# WiFi_Board_R1_0.net
KiCad netlist of a schematic drawn in EAGLE
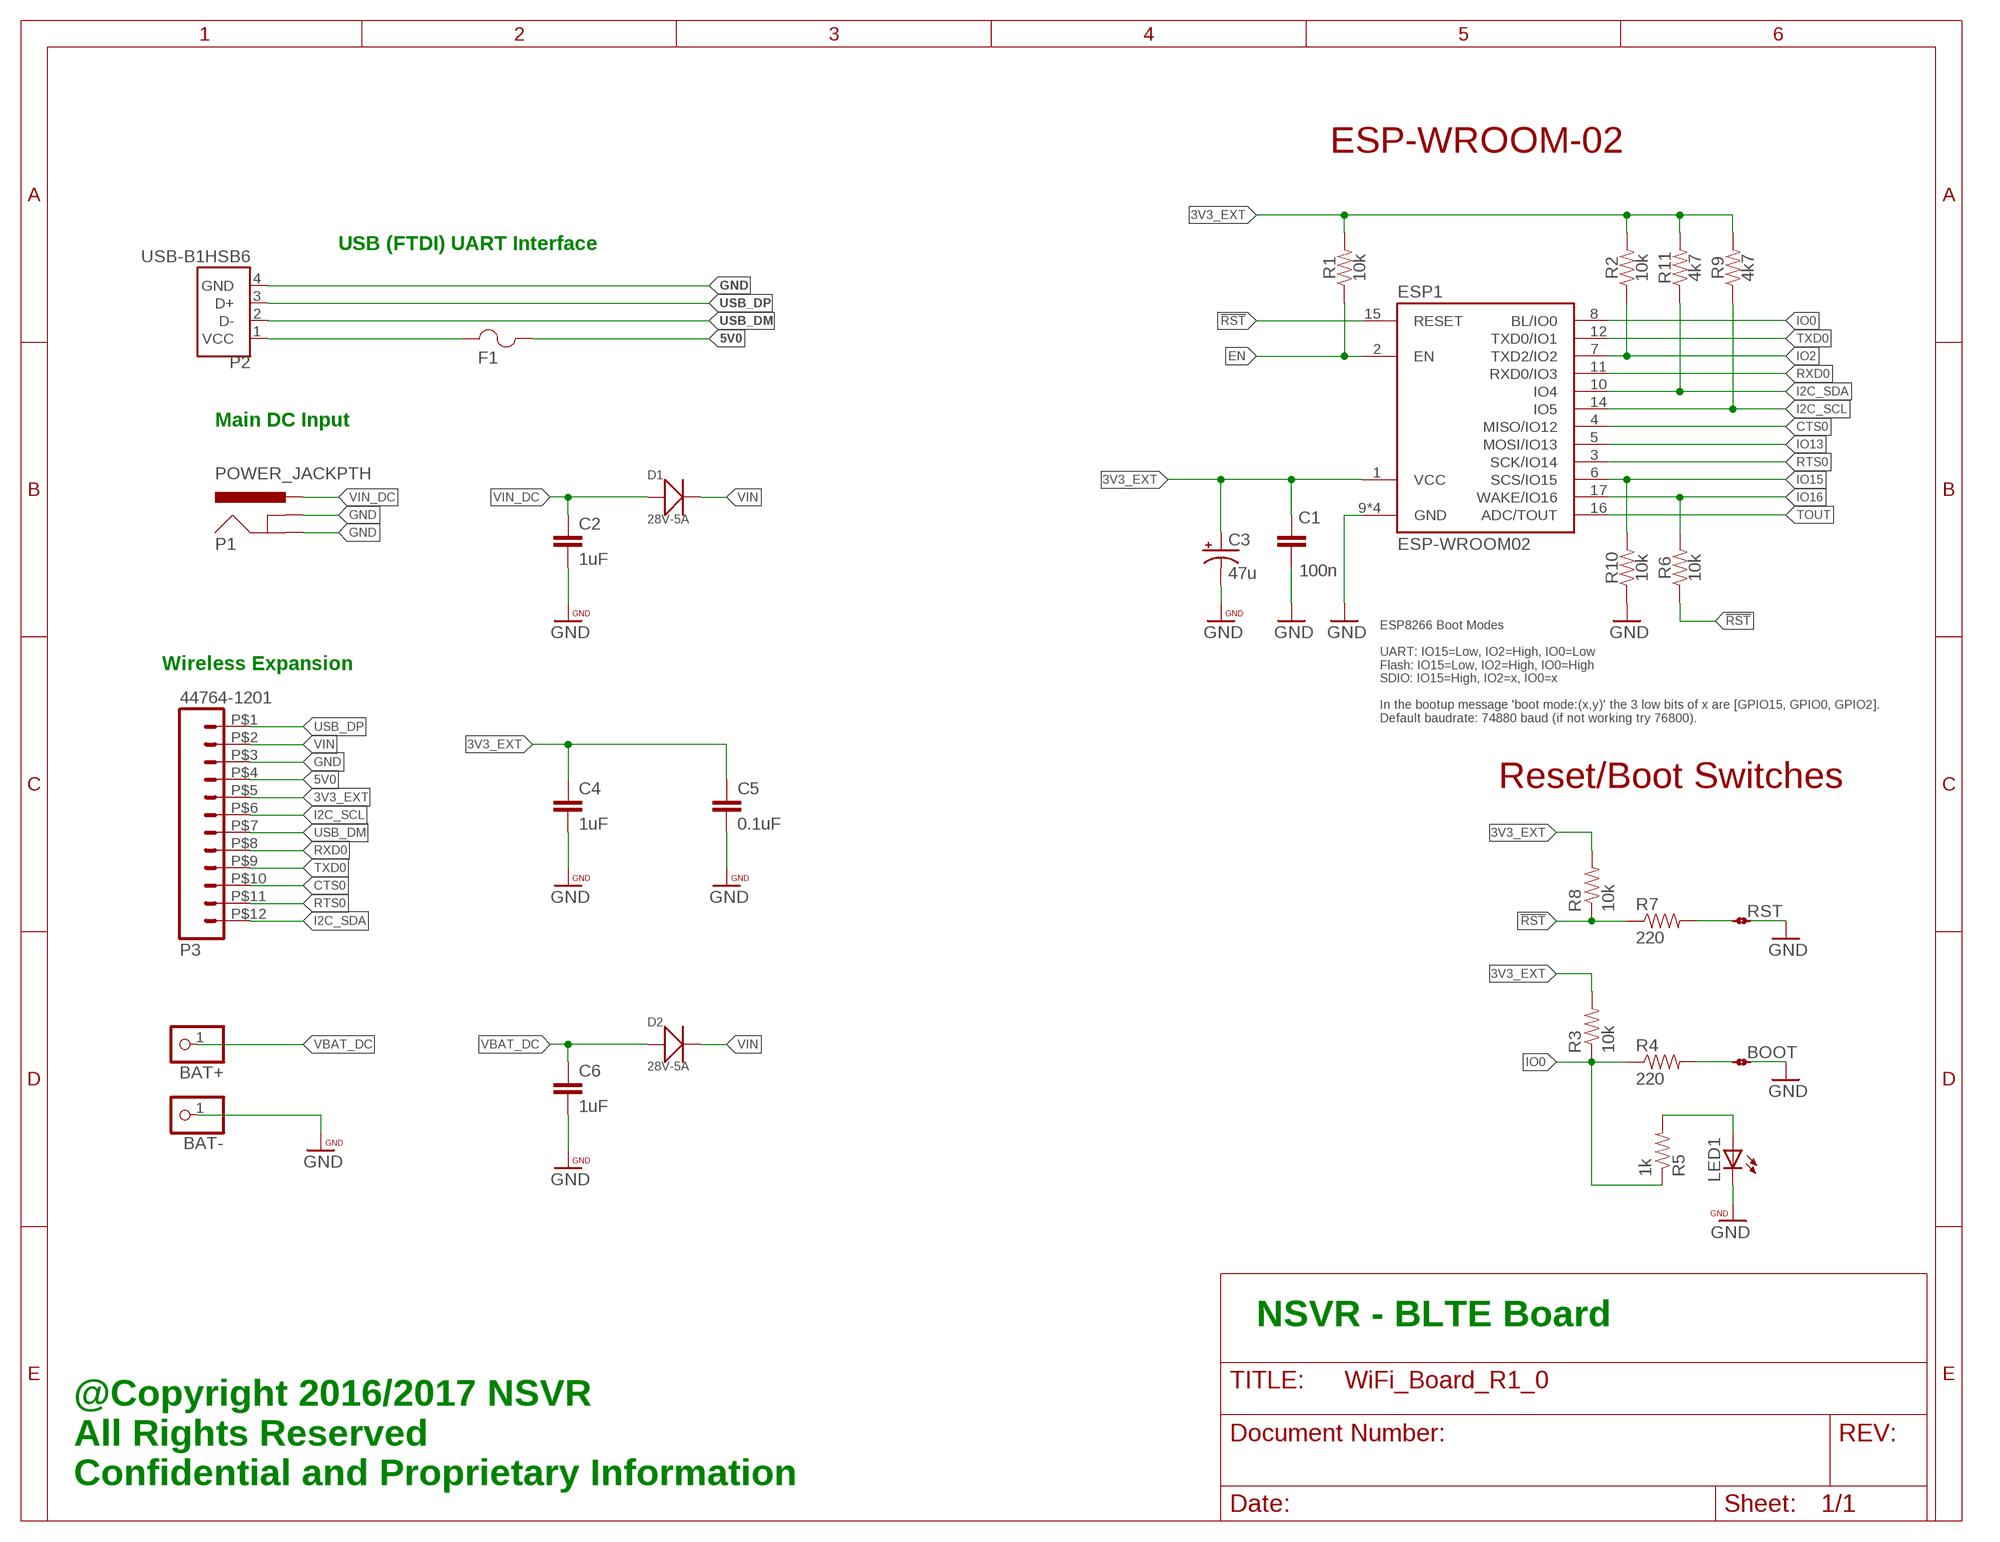
[diagram p0: schematic, sheet 1]

(export (version "E")
  (design (tool "Eeschema 10.0.6"))
  (components
    (comp (ref "BAT+")
      (value "WPAD-1-PTH")
      (footprint "eagle-import:WPAD-1-PTH-2.54")
      (libsource (lib "eagle-import") (part "WPAD-1-PTH"))
    )
    (comp (ref "BAT-")
      (value "WPAD-1-PTH")
      (footprint "eagle-import:WPAD-1-PTH-2.54")
      (libsource (lib "eagle-import") (part "WPAD-1-PTH"))
    )
    (comp (ref "BOOT")
      (value "JMP-2-NO-PTH")
      (footprint "eagle-import:JMP-2-NO-PTH-2.54")
      (libsource (lib "eagle-import") (part "JMP-2-NO-PTH"))
    )
    (comp (ref "C1")
      (value "100n")
      (footprint "eagle-import:0402-CAP")
      (libsource (lib "eagle-import") (part "CAP0402-CAP"))
    )
    (comp (ref "C2")
      (value "1uF")
      (footprint "eagle-import:0402-CAP")
      (libsource (lib "eagle-import") (part "CAP0402-CAP"))
    )
    (comp (ref "C3")
      (value "47u")
      (footprint "eagle-import:PANASONIC_D")
      (libsource (lib "eagle-import") (part "CAP_POLD"))
    )
    (comp (ref "C4")
      (value "1uF")
      (footprint "eagle-import:0402-CAP")
      (libsource (lib "eagle-import") (part "CAP0402-CAP"))
    )
    (comp (ref "C5")
      (value "0.1uF")
      (footprint "eagle-import:0402-CAP")
      (libsource (lib "eagle-import") (part "CAP0402-CAP"))
    )
    (comp (ref "C6")
      (value "1uF")
      (footprint "eagle-import:0402-CAP")
      (libsource (lib "eagle-import") (part "CAP0402-CAP"))
    )
    (comp (ref "D1")
      (value "28V-5A")
      (footprint "eagle-import:DO-214AA")
      (fields (field (name "MPN") "SS54B"))
      (libsource (lib "eagle-import") (part "SMD-DIODE-SCHOTTKY-28V-5A(DO-214AA)"))
    )
    (comp (ref "D2")
      (value "28V-5A")
      (footprint "eagle-import:DO-214AA")
      (fields (field (name "MPN") "SS54B"))
      (libsource (lib "eagle-import") (part "SMD-DIODE-SCHOTTKY-28V-5A(DO-214AA)"))
    )
    (comp (ref "ESP1")
      (value "ESP-WROOM02")
      (footprint "eagle-import:ESP-WROOM02")
      (libsource (lib "eagle-import") (part "ESP-WROOM02"))
    )
    (comp (ref "F1")
      (value "1206L050YR")
      (footprint "eagle-import:1206LSERIES")
      (fields (field (name "COPYRIGHT") "Copyright C 2015 Accelerated Designs. All rights reserved"))
      (libsource (lib "eagle-import") (part "1206L050YR"))
    )
    (comp (ref "LED1")
      (value "LEDCHIP-LED0603")
      (footprint "eagle-import:CHIP-LED0603")
      (libsource (lib "eagle-import") (part "LEDCHIP-LED0603"))
    )
    (comp (ref "P1")
      (value "POWER_JACKPTH")
      (footprint "eagle-import:POWER_JACK_PTH")
      (libsource (lib "eagle-import") (part "POWER_JACKPTH"))
    )
    (comp (ref "P2")
      (value "USB-B1HSB6")
      (footprint "eagle-import:OST_USB-B1HSB6")
      (fields (field (name "MF") "On Shore Technology"))
      (libsource (lib "eagle-import") (part "USB-B1HSB6"))
    )
    (comp (ref "P3")
      (value "44764-1201")
      (footprint "eagle-import:44764-1201")
      (libsource (lib "eagle-import") (part "44764-1201"))
    )
    (comp (ref "R1")
      (value "10k")
      (footprint "eagle-import:EIA-0402")
      (libsource (lib "eagle-import") (part "RESISTOR0402-TYP"))
    )
    (comp (ref "R2")
      (value "10k")
      (footprint "eagle-import:EIA-0402")
      (libsource (lib "eagle-import") (part "RESISTOR0402-TYP"))
    )
    (comp (ref "R3")
      (value "10k")
      (footprint "eagle-import:EIA-0402")
      (libsource (lib "eagle-import") (part "RESISTOR0402-TYP"))
    )
    (comp (ref "R4")
      (value "220")
      (footprint "eagle-import:EIA-0402")
      (libsource (lib "eagle-import") (part "RESISTOR0402-TYP"))
    )
    (comp (ref "R5")
      (value "1k")
      (footprint "eagle-import:EIA-0402")
      (libsource (lib "eagle-import") (part "RESISTOR0402-TYP"))
    )
    (comp (ref "R6")
      (value "10k")
      (footprint "eagle-import:EIA-0402")
      (libsource (lib "eagle-import") (part "RESISTOR0402-TYP"))
    )
    (comp (ref "R7")
      (value "220")
      (footprint "eagle-import:EIA-0402")
      (libsource (lib "eagle-import") (part "RESISTOR0402-TYP"))
    )
    (comp (ref "R8")
      (value "10k")
      (footprint "eagle-import:EIA-0402")
      (libsource (lib "eagle-import") (part "RESISTOR0402-TYP"))
    )
    (comp (ref "R9")
      (value "4k7")
      (footprint "eagle-import:EIA-0402")
      (libsource (lib "eagle-import") (part "RESISTOR0402-TYP"))
    )
    (comp (ref "R10")
      (value "10k")
      (footprint "eagle-import:EIA-0402")
      (libsource (lib "eagle-import") (part "RESISTOR0402-TYP"))
    )
    (comp (ref "R11")
      (value "4k7")
      (footprint "eagle-import:EIA-0402")
      (libsource (lib "eagle-import") (part "RESISTOR0402-TYP"))
    )
    (comp (ref "RST")
      (value "JMP-2-NO-PTH")
      (footprint "eagle-import:JMP-2-NO-PTH-2.54")
      (libsource (lib "eagle-import") (part "JMP-2-NO-PTH"))
    )
  )
  (nets
    (net (code "1") (name "/~{RST}") (class "Default")
      (node (ref "ESP1") (pin "15") (pinfunction "RESET_15") (pintype "bidirectional"))
      (node (ref "R6") (pin "1") (pinfunction "1_1") (pintype "passive"))
      (node (ref "R7") (pin "1") (pinfunction "1_1") (pintype "passive"))
      (node (ref "R8") (pin "1") (pinfunction "1_1") (pintype "passive"))
    )
    (net (code "2") (name "3V3_EXT") (class "Default")
      (node (ref "C1") (pin "2") (pinfunction "2_2") (pintype "passive"))
      (node (ref "C3") (pin "+") (pinfunction "+_+") (pintype "passive"))
      (node (ref "C4") (pin "1") (pinfunction "1_1") (pintype "passive"))
      (node (ref "C5") (pin "1") (pinfunction "1_1") (pintype "passive"))
      (node (ref "ESP1") (pin "1") (pinfunction "VCC_1") (pintype "power_in"))
      (node (ref "P3") (pin "P$5") (pinfunction "5_P$5") (pintype "passive"))
      (node (ref "R1") (pin "2") (pinfunction "2_2") (pintype "passive"))
      (node (ref "R11") (pin "2") (pinfunction "2_2") (pintype "passive"))
      (node (ref "R2") (pin "2") (pinfunction "2_2") (pintype "passive"))
      (node (ref "R3") (pin "2") (pinfunction "2_2") (pintype "passive"))
      (node (ref "R8") (pin "2") (pinfunction "2_2") (pintype "passive"))
      (node (ref "R9") (pin "2") (pinfunction "2_2") (pintype "passive"))
    )
    (net (code "3") (name "5V0") (class "Default")
      (node (ref "F1") (pin "2") (pinfunction "2_2") (pintype "passive"))
      (node (ref "P3") (pin "P$4") (pinfunction "4_P$4") (pintype "passive"))
    )
    (net (code "4") (name "CTS0") (class "Default")
      (node (ref "ESP1") (pin "4") (pinfunction "MISO/IO12_4") (pintype "bidirectional"))
      (node (ref "P3") (pin "P$10") (pinfunction "10_P$10") (pintype "passive"))
    )
    (net (code "5") (name "EN") (class "Default")
      (node (ref "ESP1") (pin "2") (pinfunction "EN_2") (pintype "bidirectional"))
      (node (ref "R1") (pin "1") (pinfunction "1_1") (pintype "passive"))
    )
    (net (code "6") (name "GND") (class "Default")
      (node (ref "BAT-") (pin "1") (pinfunction "1_1") (pintype "passive"))
      (node (ref "BOOT") (pin "2") (pinfunction "2_2") (pintype "passive"))
      (node (ref "C1") (pin "1") (pinfunction "1_1") (pintype "passive"))
      (node (ref "C2") (pin "2") (pinfunction "2_2") (pintype "passive"))
      (node (ref "C3") (pin "-") (pinfunction "-_-") (pintype "passive"))
      (node (ref "C4") (pin "2") (pinfunction "2_2") (pintype "passive"))
      (node (ref "C5") (pin "2") (pinfunction "2_2") (pintype "passive"))
      (node (ref "C6") (pin "2") (pinfunction "2_2") (pintype "passive"))
      (node (ref "ESP1") (pin "13") (pinfunction "GND_13") (pintype "power_in"))
      (node (ref "ESP1") (pin "18") (pinfunction "GND_18") (pintype "power_in"))
      (node (ref "ESP1") (pin "9") (pinfunction "GND_9") (pintype "power_in"))
      (node (ref "ESP1") (pin "TP") (pinfunction "GND_TP") (pintype "power_in"))
      (node (ref "LED1") (pin "C") (pinfunction "C_C") (pintype "passive"))
      (node (ref "P1") (pin "GND") (pinfunction "GND_GND") (pintype "bidirectional"))
      (node (ref "P1") (pin "GNDBREAK") (pinfunction "GNDBREAK_GNDBREAK") (pintype "bidirectional"))
      (node (ref "P2") (pin "4") (pinfunction "GND_4") (pintype "power_in"))
      (node (ref "P3") (pin "P$3") (pinfunction "3_P$3") (pintype "passive"))
      (node (ref "R10") (pin "1") (pinfunction "1_1") (pintype "passive"))
      (node (ref "RST") (pin "2") (pinfunction "2_2") (pintype "passive"))
    )
    (net (code "7") (name "I2C_SCL") (class "Default")
      (node (ref "ESP1") (pin "14") (pinfunction "IO5_14") (pintype "bidirectional"))
      (node (ref "P3") (pin "P$6") (pinfunction "6_P$6") (pintype "passive"))
      (node (ref "R9") (pin "1") (pinfunction "1_1") (pintype "passive"))
    )
    (net (code "8") (name "I2C_SDA") (class "Default")
      (node (ref "ESP1") (pin "10") (pinfunction "IO4_10") (pintype "bidirectional"))
      (node (ref "P3") (pin "P$12") (pinfunction "12_P$12") (pintype "passive"))
      (node (ref "R11") (pin "1") (pinfunction "1_1") (pintype "passive"))
    )
    (net (code "9") (name "IO0") (class "Default")
      (node (ref "ESP1") (pin "8") (pinfunction "BL/IO0_8") (pintype "bidirectional"))
      (node (ref "R3") (pin "1") (pinfunction "1_1") (pintype "passive"))
      (node (ref "R4") (pin "1") (pinfunction "1_1") (pintype "passive"))
      (node (ref "R5") (pin "1") (pinfunction "1_1") (pintype "passive"))
    )
    (net (code "10") (name "IO2") (class "Default")
      (node (ref "ESP1") (pin "7") (pinfunction "TXD2/IO2_7") (pintype "bidirectional"))
      (node (ref "R2") (pin "1") (pinfunction "1_1") (pintype "passive"))
    )
    (net (code "11") (name "IO13") (class "Default")
      (node (ref "ESP1") (pin "5") (pinfunction "MOSI/IO13_5") (pintype "bidirectional"))
    )
    (net (code "12") (name "IO15") (class "Default")
      (node (ref "ESP1") (pin "6") (pinfunction "SCS/IO15_6") (pintype "bidirectional"))
      (node (ref "R10") (pin "2") (pinfunction "2_2") (pintype "passive"))
    )
    (net (code "13") (name "IO16") (class "Default")
      (node (ref "ESP1") (pin "17") (pinfunction "WAKE/IO16_17") (pintype "bidirectional"))
      (node (ref "R6") (pin "2") (pinfunction "2_2") (pintype "passive"))
    )
    (net (code "14") (name "Net-(BOOT-Pad1)") (class "Default")
      (node (ref "BOOT") (pin "1") (pinfunction "1_1") (pintype "passive"))
      (node (ref "R4") (pin "2") (pinfunction "2_2") (pintype "passive"))
    )
    (net (code "15") (name "Net-(LED1-PadA)") (class "Default")
      (node (ref "LED1") (pin "A") (pinfunction "A_A") (pintype "passive"))
      (node (ref "R5") (pin "2") (pinfunction "2_2") (pintype "passive"))
    )
    (net (code "16") (name "Net-(P2-VCC)") (class "Default")
      (node (ref "F1") (pin "1") (pinfunction "1_1") (pintype "passive"))
      (node (ref "P2") (pin "1") (pinfunction "VCC_1") (pintype "power_in"))
    )
    (net (code "17") (name "Net-(R7-Pad2)") (class "Default")
      (node (ref "R7") (pin "2") (pinfunction "2_2") (pintype "passive"))
      (node (ref "RST") (pin "1") (pinfunction "1_1") (pintype "passive"))
    )
    (net (code "18") (name "RTS0") (class "Default")
      (node (ref "ESP1") (pin "3") (pinfunction "SCK/IO14_3") (pintype "bidirectional"))
      (node (ref "P3") (pin "P$11") (pinfunction "11_P$11") (pintype "passive"))
    )
    (net (code "19") (name "RXD0") (class "Default")
      (node (ref "ESP1") (pin "11") (pinfunction "RXD0/IO3_11") (pintype "bidirectional"))
      (node (ref "P3") (pin "P$8") (pinfunction "8_P$8") (pintype "passive"))
    )
    (net (code "20") (name "TOUT") (class "Default")
      (node (ref "ESP1") (pin "16") (pinfunction "ADC/TOUT_16") (pintype "bidirectional"))
    )
    (net (code "21") (name "TXD0") (class "Default")
      (node (ref "ESP1") (pin "12") (pinfunction "TXD0/IO1_12") (pintype "bidirectional"))
      (node (ref "P3") (pin "P$9") (pinfunction "9_P$9") (pintype "passive"))
    )
    (net (code "22") (name "USB_DM") (class "Default")
      (node (ref "P2") (pin "2") (pinfunction "D-_2") (pintype "bidirectional"))
      (node (ref "P3") (pin "P$7") (pinfunction "7_P$7") (pintype "passive"))
    )
    (net (code "23") (name "USB_DP") (class "Default")
      (node (ref "P2") (pin "3") (pinfunction "D+_3") (pintype "bidirectional"))
      (node (ref "P3") (pin "P$1") (pinfunction "1_P$1") (pintype "passive"))
    )
    (net (code "24") (name "VBAT_DC") (class "Default")
      (node (ref "BAT+") (pin "1") (pinfunction "1_1") (pintype "passive"))
      (node (ref "C6") (pin "1") (pinfunction "1_1") (pintype "passive"))
      (node (ref "D2") (pin "+") (pinfunction "+_+") (pintype "passive"))
    )
    (net (code "25") (name "VIN") (class "Default")
      (node (ref "D1") (pin "-") (pinfunction "-_-") (pintype "passive"))
      (node (ref "D2") (pin "-") (pinfunction "-_-") (pintype "passive"))
      (node (ref "P3") (pin "P$2") (pinfunction "2_P$2") (pintype "passive"))
    )
    (net (code "26") (name "VIN_DC") (class "Default")
      (node (ref "C2") (pin "1") (pinfunction "1_1") (pintype "passive"))
      (node (ref "D1") (pin "+") (pinfunction "+_+") (pintype "passive"))
      (node (ref "P1") (pin "PWR") (pinfunction "PWR_PWR") (pintype "bidirectional"))
    )
  )
)
